# FSMC.net
KiCad netlist of a schematic drawn in Altium Designer
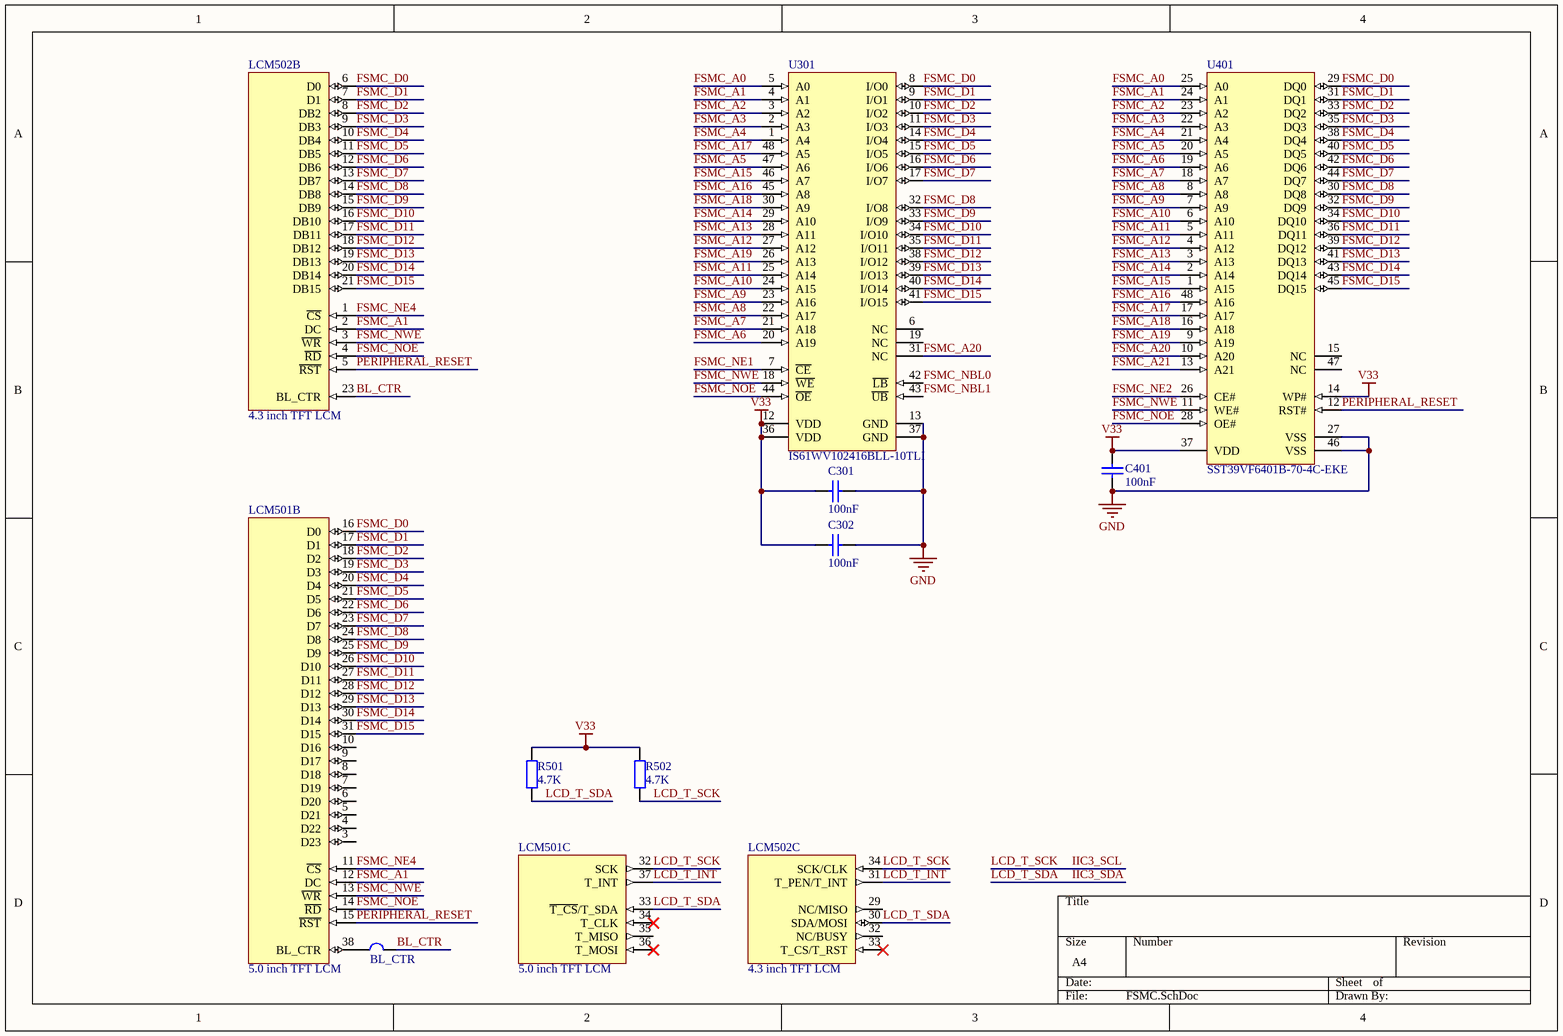
[diagram p0: FSMC.SchDoc]

(export (version "E")
  (design (tool "Eeschema 10.0.6"))
  (components
    (comp (ref "BL_CTR") (value "Switch") (footprint "SWITCH") (libsource (lib "Misc") (part "Switch")))
    (comp (ref "C301")
      (value "100nF")
      (footprint "0603C")
      (description "MLCC")
      (libsource (lib "Misc") (part "MLCC"))
    )
    (comp (ref "C302")
      (value "100nF")
      (footprint "0603C")
      (description "MLCC")
      (libsource (lib "Misc") (part "MLCC"))
    )
    (comp (ref "C401")
      (value "100nF")
      (footprint "0603C")
      (description "MLCC")
      (libsource (lib "Misc") (part "MLCC"))
    )
    (comp (ref "LCM501")
      (value "5.0 inch TFT LCM")
      (footprint "LCM5.0")
      (libsource (lib "LCM") (part "LCM5.0"))
    )
    (comp (ref "LCM502")
      (value "4.3 inch TFT LCM")
      (footprint "LCM4.3_ATK")
      (libsource (lib "LCM") (part "LCM4.3_ATK"))
    )
    (comp (ref "R501")
      (value "4.7K")
      (footprint "0603R")
      (description "Resistor")
      (libsource (lib "Misc") (part "Resistor"))
    )
    (comp (ref "R502")
      (value "4.7K")
      (footprint "0603R")
      (description "Resistor")
      (libsource (lib "Misc") (part "Resistor"))
    )
    (comp (ref "U301")
      (value "IS61WV102416BLL-10TLI")
      (footprint "ISSI-TSOP-1-48-12000X20000DE_N")
      (fields (field (name "MANUFACTURER") "Integrated Silicon Solution Inc (ISSI)"))
      (libsource (lib "Altium Content Vault") (part "CMP-0513-00250-1"))
    )
    (comp (ref "U401")
      (value "SST39VF6401B-70-4C-EKE")
      (footprint "MCHP-TSOP-EK48_N")
      (description "64 Mbit Multi-Purpose Flash Plus, 2.7 to 3.6 V, 0 to 70 degC, 48-pin TSOP (EK48), Tray")
      (fields (field (name "MANUFACTURER") "Microchip"))
      (libsource (lib "Altium Content Vault") (part "CMP-0378-00196-1"))
    )
  )
  (nets
    (net (code "1") (name "/BL_CTR") (class "Default")
      (node (ref "BL_CTR") (pin "2") (pintype "passive"))
      (node (ref "LCM502") (pin "23") (pinfunction "BL_CTR_23") (pintype "input"))
    )
    (net (code "2") (name "/FSMC_A0") (class "Default")
      (node (ref "U301") (pin "5") (pinfunction "A0_5") (pintype "input"))
      (node (ref "U401") (pin "25") (pinfunction "A0_25") (pintype "input"))
    )
    (net (code "3") (name "/FSMC_A1") (class "Default")
      (node (ref "LCM501") (pin "12") (pinfunction "DC_12") (pintype "input"))
      (node (ref "LCM502") (pin "2") (pinfunction "DC_2") (pintype "input"))
      (node (ref "U301") (pin "4") (pinfunction "A1_4") (pintype "input"))
      (node (ref "U401") (pin "24") (pinfunction "A1_24") (pintype "input"))
    )
    (net (code "4") (name "/FSMC_A2") (class "Default")
      (node (ref "U301") (pin "3") (pinfunction "A2_3") (pintype "input"))
      (node (ref "U401") (pin "23") (pinfunction "A2_23") (pintype "input"))
    )
    (net (code "5") (name "/FSMC_A3") (class "Default")
      (node (ref "U301") (pin "2") (pinfunction "A3_2") (pintype "input"))
      (node (ref "U401") (pin "22") (pinfunction "A3_22") (pintype "input"))
    )
    (net (code "6") (name "/FSMC_A4") (class "Default")
      (node (ref "U301") (pin "1") (pinfunction "A4_1") (pintype "input"))
      (node (ref "U401") (pin "21") (pinfunction "A4_21") (pintype "input"))
    )
    (net (code "7") (name "/FSMC_A5") (class "Default")
      (node (ref "U301") (pin "47") (pinfunction "A6_47") (pintype "input"))
      (node (ref "U401") (pin "20") (pinfunction "A5_20") (pintype "input"))
    )
    (net (code "8") (name "/FSMC_A6") (class "Default")
      (node (ref "U301") (pin "20") (pinfunction "A19_20") (pintype "input"))
      (node (ref "U401") (pin "19") (pinfunction "A6_19") (pintype "input"))
    )
    (net (code "9") (name "/FSMC_A7") (class "Default")
      (node (ref "U301") (pin "21") (pinfunction "A18_21") (pintype "input"))
      (node (ref "U401") (pin "18") (pinfunction "A7_18") (pintype "input"))
    )
    (net (code "10") (name "/FSMC_A8") (class "Default")
      (node (ref "U301") (pin "22") (pinfunction "A17_22") (pintype "input"))
      (node (ref "U401") (pin "8") (pinfunction "A8_8") (pintype "input"))
    )
    (net (code "11") (name "/FSMC_A9") (class "Default")
      (node (ref "U301") (pin "23") (pinfunction "A16_23") (pintype "input"))
      (node (ref "U401") (pin "7") (pinfunction "A9_7") (pintype "input"))
    )
    (net (code "12") (name "/FSMC_A10") (class "Default")
      (node (ref "U301") (pin "24") (pinfunction "A15_24") (pintype "input"))
      (node (ref "U401") (pin "6") (pinfunction "A10_6") (pintype "input"))
    )
    (net (code "13") (name "/FSMC_A11") (class "Default")
      (node (ref "U301") (pin "25") (pinfunction "A14_25") (pintype "input"))
      (node (ref "U401") (pin "5") (pinfunction "A11_5") (pintype "input"))
    )
    (net (code "14") (name "/FSMC_A12") (class "Default")
      (node (ref "U301") (pin "27") (pinfunction "A12_27") (pintype "input"))
      (node (ref "U401") (pin "4") (pinfunction "A12_4") (pintype "input"))
    )
    (net (code "15") (name "/FSMC_A13") (class "Default")
      (node (ref "U301") (pin "28") (pinfunction "A11_28") (pintype "input"))
      (node (ref "U401") (pin "3") (pinfunction "A13_3") (pintype "input"))
    )
    (net (code "16") (name "/FSMC_A14") (class "Default")
      (node (ref "U301") (pin "29") (pinfunction "A10_29") (pintype "input"))
      (node (ref "U401") (pin "2") (pinfunction "A14_2") (pintype "input"))
    )
    (net (code "17") (name "/FSMC_A15") (class "Default")
      (node (ref "U301") (pin "46") (pinfunction "A7_46") (pintype "input"))
      (node (ref "U401") (pin "1") (pinfunction "A15_1") (pintype "input"))
    )
    (net (code "18") (name "/FSMC_A16") (class "Default")
      (node (ref "U301") (pin "45") (pinfunction "A8_45") (pintype "input"))
      (node (ref "U401") (pin "48") (pinfunction "A16_48") (pintype "input"))
    )
    (net (code "19") (name "/FSMC_A17") (class "Default")
      (node (ref "U301") (pin "48") (pinfunction "A5_48") (pintype "input"))
      (node (ref "U401") (pin "17") (pinfunction "A17_17") (pintype "input"))
    )
    (net (code "20") (name "/FSMC_A18") (class "Default")
      (node (ref "U301") (pin "30") (pinfunction "A9_30") (pintype "input"))
      (node (ref "U401") (pin "16") (pinfunction "A18_16") (pintype "input"))
    )
    (net (code "21") (name "/FSMC_A19") (class "Default")
      (node (ref "U301") (pin "26") (pinfunction "A13_26") (pintype "input"))
      (node (ref "U401") (pin "9") (pinfunction "A19_9") (pintype "input"))
    )
    (net (code "22") (name "/FSMC_A20") (class "Default")
      (node (ref "U301") (pin "31") (pinfunction "NC_31") (pintype "passive"))
      (node (ref "U401") (pin "10") (pinfunction "A20_10") (pintype "input"))
    )
    (net (code "23") (name "/FSMC_A21") (class "Default")
      (node (ref "U401") (pin "13") (pinfunction "A21_13") (pintype "input"))
    )
    (net (code "24") (name "/FSMC_D0") (class "Default")
      (node (ref "LCM501") (pin "16") (pinfunction "D0_16") (pintype "bidirectional"))
      (node (ref "LCM502") (pin "6") (pinfunction "D0_6") (pintype "bidirectional"))
      (node (ref "U301") (pin "8") (pinfunction "I/O0_8") (pintype "bidirectional"))
      (node (ref "U401") (pin "29") (pinfunction "DQ0_29") (pintype "bidirectional"))
    )
    (net (code "25") (name "/FSMC_D1") (class "Default")
      (node (ref "LCM501") (pin "17") (pinfunction "D1_17") (pintype "bidirectional"))
      (node (ref "LCM502") (pin "7") (pinfunction "D1_7") (pintype "bidirectional"))
      (node (ref "U301") (pin "9") (pinfunction "I/O1_9") (pintype "bidirectional"))
      (node (ref "U401") (pin "31") (pinfunction "DQ1_31") (pintype "bidirectional"))
    )
    (net (code "26") (name "/FSMC_D2") (class "Default")
      (node (ref "LCM501") (pin "18") (pinfunction "D2_18") (pintype "bidirectional"))
      (node (ref "LCM502") (pin "8") (pinfunction "DB2_8") (pintype "bidirectional"))
      (node (ref "U301") (pin "10") (pinfunction "I/O2_10") (pintype "bidirectional"))
      (node (ref "U401") (pin "33") (pinfunction "DQ2_33") (pintype "bidirectional"))
    )
    (net (code "27") (name "/FSMC_D3") (class "Default")
      (node (ref "LCM501") (pin "19") (pinfunction "D3_19") (pintype "bidirectional"))
      (node (ref "LCM502") (pin "9") (pinfunction "DB3_9") (pintype "bidirectional"))
      (node (ref "U301") (pin "11") (pinfunction "I/O3_11") (pintype "bidirectional"))
      (node (ref "U401") (pin "35") (pinfunction "DQ3_35") (pintype "bidirectional"))
    )
    (net (code "28") (name "/FSMC_D4") (class "Default")
      (node (ref "LCM501") (pin "20") (pinfunction "D4_20") (pintype "bidirectional"))
      (node (ref "LCM502") (pin "10") (pinfunction "DB4_10") (pintype "bidirectional"))
      (node (ref "U301") (pin "14") (pinfunction "I/O4_14") (pintype "bidirectional"))
      (node (ref "U401") (pin "38") (pinfunction "DQ4_38") (pintype "bidirectional"))
    )
    (net (code "29") (name "/FSMC_D5") (class "Default")
      (node (ref "LCM501") (pin "21") (pinfunction "D5_21") (pintype "bidirectional"))
      (node (ref "LCM502") (pin "11") (pinfunction "DB5_11") (pintype "bidirectional"))
      (node (ref "U301") (pin "15") (pinfunction "I/O5_15") (pintype "bidirectional"))
      (node (ref "U401") (pin "40") (pinfunction "DQ5_40") (pintype "bidirectional"))
    )
    (net (code "30") (name "/FSMC_D6") (class "Default")
      (node (ref "LCM501") (pin "22") (pinfunction "D6_22") (pintype "bidirectional"))
      (node (ref "LCM502") (pin "12") (pinfunction "DB6_12") (pintype "bidirectional"))
      (node (ref "U301") (pin "16") (pinfunction "I/O6_16") (pintype "bidirectional"))
      (node (ref "U401") (pin "42") (pinfunction "DQ6_42") (pintype "bidirectional"))
    )
    (net (code "31") (name "/FSMC_D7") (class "Default")
      (node (ref "LCM501") (pin "23") (pinfunction "D7_23") (pintype "bidirectional"))
      (node (ref "LCM502") (pin "13") (pinfunction "DB7_13") (pintype "bidirectional"))
      (node (ref "U301") (pin "17") (pinfunction "I/O7_17") (pintype "bidirectional"))
      (node (ref "U401") (pin "44") (pinfunction "DQ7_44") (pintype "bidirectional"))
    )
    (net (code "32") (name "/FSMC_D8") (class "Default")
      (node (ref "LCM501") (pin "24") (pinfunction "D8_24") (pintype "bidirectional"))
      (node (ref "LCM502") (pin "14") (pinfunction "DB8_14") (pintype "bidirectional"))
      (node (ref "U301") (pin "32") (pinfunction "I/O8_32") (pintype "bidirectional"))
      (node (ref "U401") (pin "30") (pinfunction "DQ8_30") (pintype "bidirectional"))
    )
    (net (code "33") (name "/FSMC_D9") (class "Default")
      (node (ref "LCM501") (pin "25") (pinfunction "D9_25") (pintype "bidirectional"))
      (node (ref "LCM502") (pin "15") (pinfunction "DB9_15") (pintype "bidirectional"))
      (node (ref "U301") (pin "33") (pinfunction "I/O9_33") (pintype "bidirectional"))
      (node (ref "U401") (pin "32") (pinfunction "DQ9_32") (pintype "bidirectional"))
    )
    (net (code "34") (name "/FSMC_D10") (class "Default")
      (node (ref "LCM501") (pin "26") (pinfunction "D10_26") (pintype "bidirectional"))
      (node (ref "LCM502") (pin "16") (pinfunction "DB10_16") (pintype "bidirectional"))
      (node (ref "U301") (pin "34") (pinfunction "I/O10_34") (pintype "bidirectional"))
      (node (ref "U401") (pin "34") (pinfunction "DQ10_34") (pintype "bidirectional"))
    )
    (net (code "35") (name "/FSMC_D11") (class "Default")
      (node (ref "LCM501") (pin "27") (pinfunction "D11_27") (pintype "bidirectional"))
      (node (ref "LCM502") (pin "17") (pinfunction "DB11_17") (pintype "bidirectional"))
      (node (ref "U301") (pin "35") (pinfunction "I/O11_35") (pintype "bidirectional"))
      (node (ref "U401") (pin "36") (pinfunction "DQ11_36") (pintype "bidirectional"))
    )
    (net (code "36") (name "/FSMC_D12") (class "Default")
      (node (ref "LCM501") (pin "28") (pinfunction "D12_28") (pintype "bidirectional"))
      (node (ref "LCM502") (pin "18") (pinfunction "DB12_18") (pintype "bidirectional"))
      (node (ref "U301") (pin "38") (pinfunction "I/O12_38") (pintype "bidirectional"))
      (node (ref "U401") (pin "39") (pinfunction "DQ12_39") (pintype "bidirectional"))
    )
    (net (code "37") (name "/FSMC_D13") (class "Default")
      (node (ref "LCM501") (pin "29") (pinfunction "D13_29") (pintype "bidirectional"))
      (node (ref "LCM502") (pin "19") (pinfunction "DB13_19") (pintype "bidirectional"))
      (node (ref "U301") (pin "39") (pinfunction "I/O13_39") (pintype "bidirectional"))
      (node (ref "U401") (pin "41") (pinfunction "DQ13_41") (pintype "bidirectional"))
    )
    (net (code "38") (name "/FSMC_D14") (class "Default")
      (node (ref "LCM501") (pin "30") (pinfunction "D14_30") (pintype "bidirectional"))
      (node (ref "LCM502") (pin "20") (pinfunction "DB14_20") (pintype "bidirectional"))
      (node (ref "U301") (pin "40") (pinfunction "I/O14_40") (pintype "bidirectional"))
      (node (ref "U401") (pin "43") (pinfunction "DQ14_43") (pintype "bidirectional"))
    )
    (net (code "39") (name "/FSMC_D15") (class "Default")
      (node (ref "LCM501") (pin "31") (pinfunction "D15_31") (pintype "bidirectional"))
      (node (ref "LCM502") (pin "21") (pinfunction "DB15_21") (pintype "bidirectional"))
      (node (ref "U301") (pin "41") (pinfunction "I/O15_41") (pintype "bidirectional"))
      (node (ref "U401") (pin "45") (pinfunction "DQ15_45") (pintype "bidirectional"))
    )
    (net (code "40") (name "/FSMC_NBL0") (class "Default")
      (node (ref "U301") (pin "42") (pinfunction "~{LB}_42") (pintype "input"))
    )
    (net (code "41") (name "/FSMC_NBL1") (class "Default")
      (node (ref "U301") (pin "43") (pinfunction "~{UB}_43") (pintype "input"))
    )
    (net (code "42") (name "/FSMC_NE1") (class "Default")
      (node (ref "U301") (pin "7") (pinfunction "~{CE}_7") (pintype "input"))
    )
    (net (code "43") (name "/FSMC_NE2") (class "Default")
      (node (ref "U401") (pin "26") (pinfunction "CE#_26") (pintype "input"))
    )
    (net (code "44") (name "/FSMC_NE4") (class "Default")
      (node (ref "LCM501") (pin "11") (pinfunction "~{CS}_11") (pintype "input"))
      (node (ref "LCM502") (pin "1") (pinfunction "~{CS}_1") (pintype "input"))
    )
    (net (code "45") (name "/FSMC_NOE") (class "Default")
      (node (ref "LCM501") (pin "14") (pinfunction "~{RD}_14") (pintype "input"))
      (node (ref "LCM502") (pin "4") (pinfunction "~{RD}_4") (pintype "input"))
      (node (ref "U301") (pin "44") (pinfunction "~{OE}_44") (pintype "input"))
      (node (ref "U401") (pin "28") (pinfunction "OE#_28") (pintype "input"))
    )
    (net (code "46") (name "/FSMC_NWE") (class "Default")
      (node (ref "LCM501") (pin "13") (pinfunction "~{WR}_13") (pintype "input"))
      (node (ref "LCM502") (pin "3") (pinfunction "~{WR}_3") (pintype "input"))
      (node (ref "U301") (pin "18") (pinfunction "~{WE}_18") (pintype "input"))
      (node (ref "U401") (pin "11") (pinfunction "WE#_11") (pintype "input"))
    )
    (net (code "47") (name "/IIC3_SCL") (class "Default")
      (node (ref "LCM501") (pin "32") (pinfunction "SCK_32") (pintype "output"))
      (node (ref "LCM502") (pin "34") (pinfunction "SCK/CLK_34") (pintype "input"))
      (node (ref "R502") (pin "1") (pinfunction "1_1") (pintype "passive"))
    )
    (net (code "48") (name "/IIC3_SDA") (class "Default")
      (node (ref "LCM501") (pin "33") (pinfunction "~{T_CS}/T_SDA_33") (pintype "input"))
      (node (ref "LCM502") (pin "30") (pinfunction "SDA/MOSI_30") (pintype "bidirectional"))
      (node (ref "R501") (pin "1") (pinfunction "1_1") (pintype "passive"))
    )
    (net (code "49") (name "/LCD_T_INT") (class "Default")
      (node (ref "LCM501") (pin "37") (pinfunction "T_INT_37") (pintype "output"))
      (node (ref "LCM502") (pin "31") (pinfunction "T_PEN/T_INT_31") (pintype "output"))
    )
    (net (code "50") (name "/PERIPHERAL_RESET") (class "Default")
      (node (ref "LCM501") (pin "15") (pinfunction "~{RST}_15") (pintype "input"))
      (node (ref "LCM502") (pin "5") (pinfunction "~{RST}_5") (pintype "input"))
      (node (ref "U401") (pin "12") (pinfunction "RST#_12") (pintype "input"))
    )
    (net (code "51") (name "GND") (class "Default")
      (node (ref "C301") (pin "2") (pinfunction "2_2") (pintype "passive"))
      (node (ref "C302") (pin "2") (pinfunction "2_2") (pintype "passive"))
      (node (ref "C401") (pin "1") (pinfunction "1_1") (pintype "passive"))
      (node (ref "U301") (pin "13") (pinfunction "GND_13") (pintype "power_in"))
      (node (ref "U301") (pin "37") (pinfunction "GND_37") (pintype "power_in"))
      (node (ref "U401") (pin "27") (pinfunction "VSS_27") (pintype "power_in"))
      (node (ref "U401") (pin "46") (pinfunction "VSS_46") (pintype "power_in"))
    )
    (net (code "52") (name "Net-(LCM501B-BL_CTR)") (class "Default")
      (node (ref "BL_CTR") (pin "1") (pintype "passive"))
      (node (ref "LCM501") (pin "38") (pinfunction "BL_CTR_38") (pintype "bidirectional"))
    )
    (net (code "53") (name "V33") (class "Default")
      (node (ref "C301") (pin "1") (pinfunction "1_1") (pintype "passive"))
      (node (ref "C302") (pin "1") (pinfunction "1_1") (pintype "passive"))
      (node (ref "C401") (pin "2") (pinfunction "2_2") (pintype "passive"))
      (node (ref "R501") (pin "2") (pinfunction "2_2") (pintype "passive"))
      (node (ref "R502") (pin "2") (pinfunction "2_2") (pintype "passive"))
      (node (ref "U301") (pin "12") (pinfunction "VDD_12") (pintype "power_in"))
      (node (ref "U301") (pin "36") (pinfunction "VDD_36") (pintype "power_in"))
      (node (ref "U401") (pin "14") (pinfunction "WP#_14") (pintype "input"))
      (node (ref "U401") (pin "37") (pinfunction "VDD_37") (pintype "power_in"))
    )
    (net (code "54") (name "unconnected-(LCM501B-D16-Pad10)") (class "Default")
      (node (ref "LCM501") (pin "10") (pinfunction "D16_10") (pintype "bidirectional"))
    )
    (net (code "55") (name "unconnected-(LCM501B-D17-Pad9)") (class "Default")
      (node (ref "LCM501") (pin "9") (pinfunction "D17_9") (pintype "bidirectional"))
    )
    (net (code "56") (name "unconnected-(LCM501B-D18-Pad8)") (class "Default")
      (node (ref "LCM501") (pin "8") (pinfunction "D18_8") (pintype "bidirectional"))
    )
    (net (code "57") (name "unconnected-(LCM501B-D19-Pad7)") (class "Default")
      (node (ref "LCM501") (pin "7") (pinfunction "D19_7") (pintype "bidirectional"))
    )
    (net (code "58") (name "unconnected-(LCM501B-D20-Pad6)") (class "Default")
      (node (ref "LCM501") (pin "6") (pinfunction "D20_6") (pintype "bidirectional"))
    )
    (net (code "59") (name "unconnected-(LCM501B-D21-Pad5)") (class "Default")
      (node (ref "LCM501") (pin "5") (pinfunction "D21_5") (pintype "bidirectional"))
    )
    (net (code "60") (name "unconnected-(LCM501B-D22-Pad4)") (class "Default")
      (node (ref "LCM501") (pin "4") (pinfunction "D22_4") (pintype "bidirectional"))
    )
    (net (code "61") (name "unconnected-(LCM501B-D23-Pad3)") (class "Default")
      (node (ref "LCM501") (pin "3") (pinfunction "D23_3") (pintype "bidirectional"))
    )
    (net (code "62") (name "unconnected-(LCM501C-T_CLK-Pad34)") (class "Default")
      (node (ref "LCM501") (pin "34") (pinfunction "T_CLK_34") (pintype "input+no_connect"))
    )
    (net (code "63") (name "unconnected-(LCM501C-T_MISO-Pad35)") (class "Default")
      (node (ref "LCM501") (pin "35") (pinfunction "T_MISO_35") (pintype "output"))
    )
    (net (code "64") (name "unconnected-(LCM501C-T_MOSI-Pad36)") (class "Default")
      (node (ref "LCM501") (pin "36") (pinfunction "T_MOSI_36") (pintype "input+no_connect"))
    )
    (net (code "65") (name "unconnected-(LCM502C-NC{slash}BUSY-Pad32)") (class "Default")
      (node (ref "LCM502") (pin "32") (pinfunction "NC/BUSY_32") (pintype "output"))
    )
    (net (code "66") (name "unconnected-(LCM502C-NC{slash}MISO-Pad29)") (class "Default")
      (node (ref "LCM502") (pin "29") (pinfunction "NC/MISO_29") (pintype "output"))
    )
    (net (code "67") (name "unconnected-(LCM502C-T_CS{slash}T_RST-Pad33)") (class "Default")
      (node (ref "LCM502") (pin "33") (pinfunction "T_CS/T_RST_33") (pintype "input+no_connect"))
    )
    (net (code "68") (name "unconnected-(U301-NC-Pad6)") (class "Default")
      (node (ref "U301") (pin "6") (pinfunction "NC_6") (pintype "passive"))
    )
    (net (code "69") (name "unconnected-(U301-NC-Pad19)") (class "Default")
      (node (ref "U301") (pin "19") (pinfunction "NC_19") (pintype "passive"))
    )
    (net (code "70") (name "unconnected-(U401-NC-Pad15)") (class "Default")
      (node (ref "U401") (pin "15") (pinfunction "NC_15") (pintype "passive"))
    )
    (net (code "71") (name "unconnected-(U401-NC-Pad47)") (class "Default")
      (node (ref "U401") (pin "47") (pinfunction "NC_47") (pintype "passive"))
    )
  )
)
